# hand.net
KiCad netlist of a schematic drawn in Altium Designer
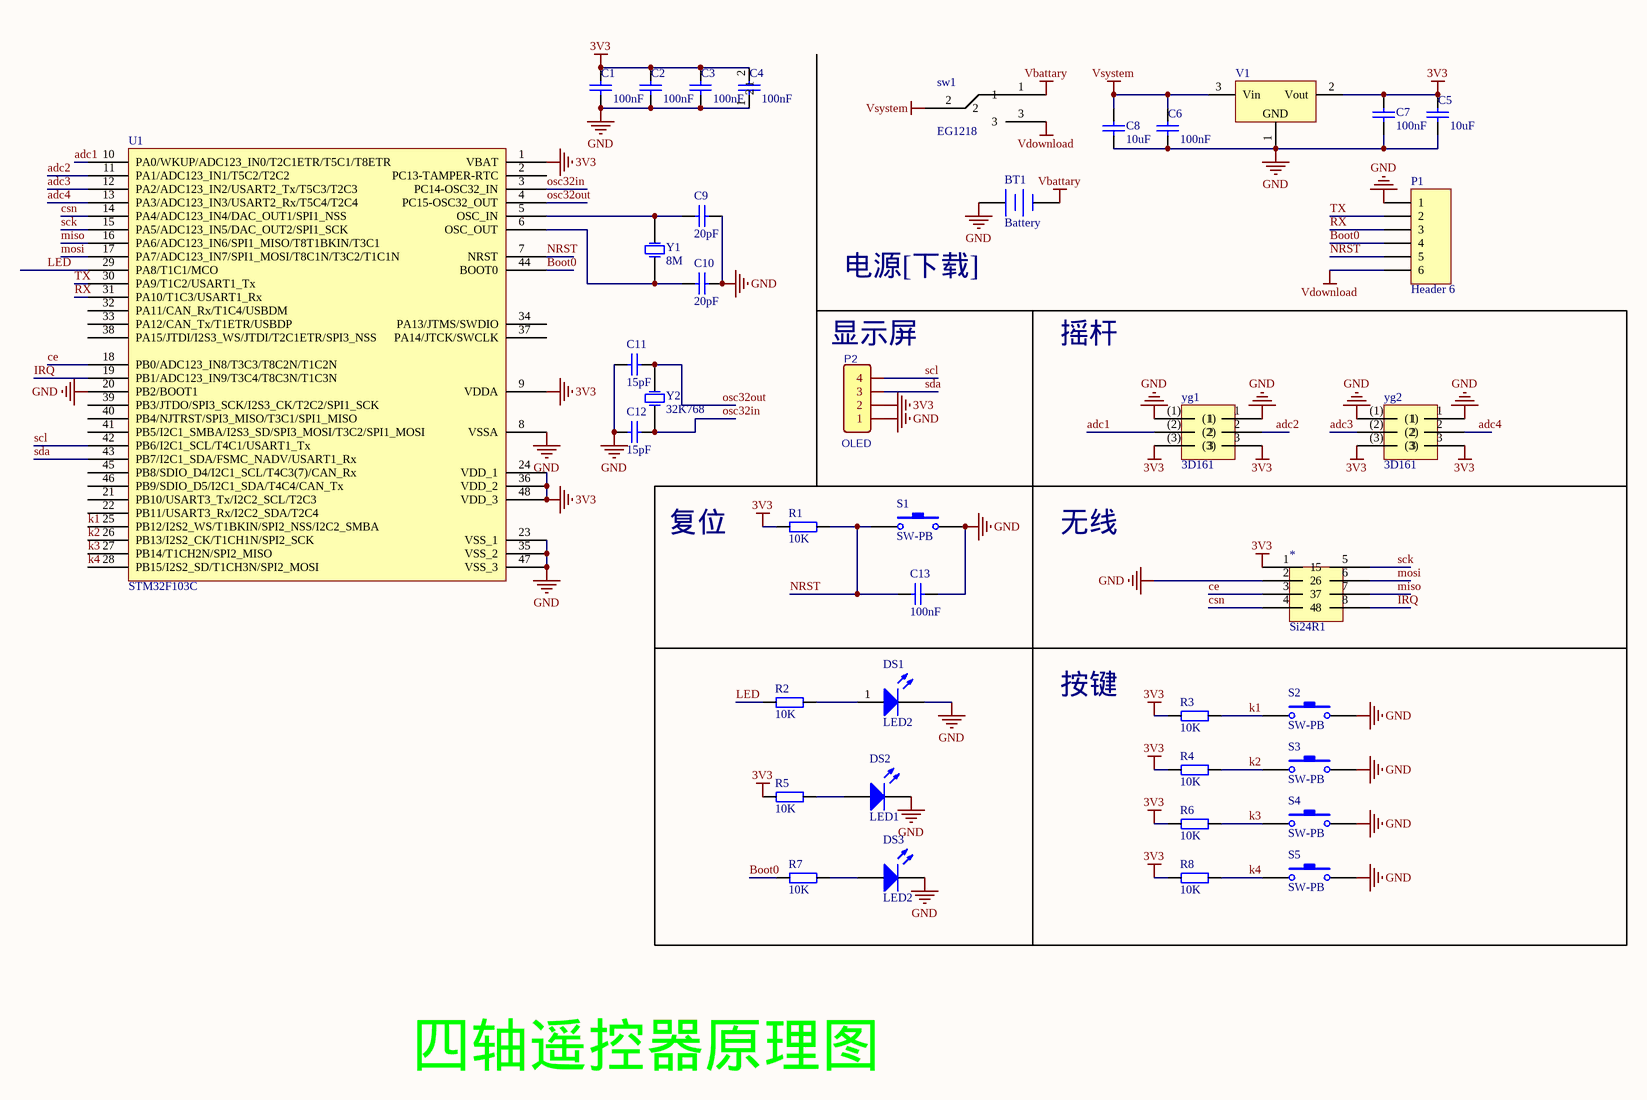
[diagram p0: hand.SchDoc]

(export (version "E")
  (design (tool "Eeschema 10.0.6"))
  (components
    (comp (ref "*")
      (value "Si24R1")
      (footprint "WIRELM-SMD_DL-SI24R1-A")
      (libsource (lib "Schlib1") (part "Si24R1"))
    )
    (comp (ref "BT1")
      (value "Battery")
      (footprint "CONN-TH_2P-P2.00_HDGC_HDGC2001WV-2P")
      (description "采用ph2.0接线端子")
      (fields (field (name "PUBLISHER") "Altium Limited"))
      (libsource (lib "Miscellaneous Devices") (part "Battery"))
    )
    (comp (ref "C1")
      (value "100nF")
      (footprint "C0603")
      (description "Capacitor")
      (fields (field (name "PUBLISHER") "Altium Limited"))
      (libsource (lib "Miscellaneous Devices") (part "Cap"))
    )
    (comp (ref "C2")
      (value "100nF")
      (footprint "C0603")
      (description "Capacitor")
      (fields (field (name "PUBLISHER") "Altium Limited"))
      (libsource (lib "Miscellaneous Devices") (part "Cap"))
    )
    (comp (ref "C3")
      (value "100nF")
      (footprint "C0603")
      (description "Capacitor")
      (fields (field (name "PUBLISHER") "Altium Limited"))
      (libsource (lib "Miscellaneous Devices") (part "Cap"))
    )
    (comp (ref "C4")
      (value "100nF")
      (footprint "C0603")
      (description "Capacitor")
      (fields (field (name "PUBLISHER") "Altium Limited"))
      (libsource (lib "") (part "Cap_1"))
    )
    (comp (ref "C5")
      (value "10uF")
      (footprint "C0603")
      (description "Capacitor")
      (fields (field (name "PUBLISHER") "Altium Limited"))
      (libsource (lib "Miscellaneous Devices") (part "Cap"))
    )
    (comp (ref "C6")
      (value "100nF")
      (footprint "C0603")
      (description "Capacitor")
      (fields (field (name "PUBLISHER") "Altium Limited"))
      (libsource (lib "Miscellaneous Devices") (part "Cap"))
    )
    (comp (ref "C7")
      (value "100nF")
      (footprint "C0603")
      (description "Capacitor")
      (fields (field (name "PUBLISHER") "Altium Limited"))
      (libsource (lib "Miscellaneous Devices") (part "Cap"))
    )
    (comp (ref "C8")
      (value "10uF")
      (footprint "C0603")
      (description "Capacitor")
      (fields (field (name "PUBLISHER") "Altium Limited"))
      (libsource (lib "Miscellaneous Devices") (part "Cap"))
    )
    (comp (ref "C9")
      (value "20pF")
      (footprint "C0603")
      (description "Capacitor")
      (fields (field (name "PUBLISHER") "Altium Limited"))
      (libsource (lib "Miscellaneous Devices") (part "Cap"))
    )
    (comp (ref "C10")
      (value "20pF")
      (footprint "C0603")
      (description "Capacitor")
      (fields (field (name "PUBLISHER") "Altium Limited"))
      (libsource (lib "Miscellaneous Devices") (part "Cap"))
    )
    (comp (ref "C11")
      (value "15pF")
      (footprint "C0603")
      (description "Capacitor")
      (fields (field (name "PUBLISHER") "Altium Limited"))
      (libsource (lib "Miscellaneous Devices") (part "Cap"))
    )
    (comp (ref "C12")
      (value "15pF")
      (footprint "C0603")
      (description "Capacitor")
      (fields (field (name "PUBLISHER") "Altium Limited"))
      (libsource (lib "Miscellaneous Devices") (part "Cap"))
    )
    (comp (ref "C13")
      (value "100nF")
      (footprint "C0603")
      (description "Capacitor")
      (fields (field (name "PUBLISHER") "Altium Limited"))
      (libsource (lib "Miscellaneous Devices") (part "Cap"))
    )
    (comp (ref "DS1")
      (value "LED2")
      (footprint "SMDLED")
      (description "Typical RED, GREEN, YELLOW, AMBER GaAs LED")
      (fields (field (name "PUBLISHER") "Altium Limited"))
      (libsource (lib "") (part "LED2_1"))
    )
    (comp (ref "DS2")
      (value "LED1")
      (footprint "SMDLED")
      (description "Typical RED, GREEN, YELLOW, AMBER GaAs LED")
      (fields (field (name "PUBLISHER") "Altium Limited"))
      (libsource (lib "朱雀F103开发板封装库") (part "LED2"))
    )
    (comp (ref "DS3")
      (value "LED2")
      (footprint "SMDLED")
      (description "Typical RED, GREEN, YELLOW, AMBER GaAs LED")
      (fields (field (name "PUBLISHER") "Altium Limited"))
      (libsource (lib "朱雀F103开发板封装库") (part "LED2"))
    )
    (comp (ref "P1")
      (value "Header 6")
      (footprint "HDR-TH_6P-P2.54-V-M-R2-C3-S2.54-1")
      (description "Header, 6-Pin")
      (fields (field (name "PUBLISHER") "Altium Limited"))
      (libsource (lib "Miscellaneous Connectors") (part "Header 6"))
    )
    (comp (ref "P2")
      (value "OLED")
      (footprint "P04A")
      (fields
        (field (name "BOM_MANUFACTURER PART") "2.54-1*4P母")
        (field (name "BOM_SUPPLIER PART") "C2718488")
        (field (name "CONTRIBUTOR") "PQG2030PQG")
      )
      (libsource (lib "altium-import") (part "root_2_OLED_"))
    )
    (comp (ref "R1") (value "10K") (footprint "0603P") (libsource (lib "朱雀F103开发板封装库") (part "R")))
    (comp (ref "R2") (value "10K") (footprint "0603P") (libsource (lib "朱雀F103开发板封装库") (part "R")))
    (comp (ref "R3") (value "10K") (footprint "0603P") (libsource (lib "朱雀F103开发板封装库") (part "R")))
    (comp (ref "R4") (value "10K") (footprint "0603P") (libsource (lib "朱雀F103开发板封装库") (part "R")))
    (comp (ref "R5") (value "10K") (footprint "0603P") (libsource (lib "朱雀F103开发板封装库") (part "R")))
    (comp (ref "R6") (value "10K") (footprint "0603P") (libsource (lib "朱雀F103开发板封装库") (part "R")))
    (comp (ref "R7") (value "10K") (footprint "0603P") (libsource (lib "朱雀F103开发板封装库") (part "R")))
    (comp (ref "R8") (value "10K") (footprint "0603P") (libsource (lib "朱雀F103开发板封装库") (part "R")))
    (comp (ref "S1")
      (value "SW-PB")
      (footprint "KEY-SMD_L3.9-W3.0-LS5.0")
      (description "Switch")
      (fields (field (name "PUBLISHER") "Altium Limited"))
      (libsource (lib "Miscellaneous Devices") (part "SW-PB"))
    )
    (comp (ref "S2")
      (value "SW-PB")
      (footprint "KEY-SMD_L3.9-W3.0-LS5.0")
      (description "Switch")
      (fields (field (name "PUBLISHER") "Altium Limited"))
      (libsource (lib "Miscellaneous Devices") (part "SW-PB"))
    )
    (comp (ref "S3")
      (value "SW-PB")
      (footprint "KEY-SMD_L3.9-W3.0-LS5.0")
      (description "Switch")
      (fields (field (name "PUBLISHER") "Altium Limited"))
      (libsource (lib "Miscellaneous Devices") (part "SW-PB"))
    )
    (comp (ref "S4")
      (value "SW-PB")
      (footprint "KEY-SMD_L3.9-W3.0-LS5.0")
      (description "Switch")
      (fields (field (name "PUBLISHER") "Altium Limited"))
      (libsource (lib "Miscellaneous Devices") (part "SW-PB"))
    )
    (comp (ref "S5")
      (value "SW-PB")
      (footprint "KEY-SMD_L3.9-W3.0-LS5.0")
      (description "Switch")
      (fields (field (name "PUBLISHER") "Altium Limited"))
      (libsource (lib "Miscellaneous Devices") (part "SW-PB"))
    )
    (comp (ref "sw1") (value "EG1218") (footprint "SW-TH_EG1218") (libsource (lib "Schlib1") (part "EG1218")))
    (comp (ref "U1")
      (value "STM32F103C")
      (footprint "LQFP-48_M")
      (description "STM32单片机48引脚")
      (libsource (lib "STM32芯片") (part "STM32F103C"))
    )
    (comp (ref "V1")
      (value "AMS1117-3V3")
      (footprint "SOT223_L")
      (description "三端稳压芯片")
      (fields (field (name "版权归属") "源创客"))
      (libsource (lib "1.3   - 电源类芯片") (part "AMS1117"))
    )
    (comp (ref "Y1")
      (value "8M")
      (footprint "XTAL(5032)")
      (description "Crystal Oscillator")
      (fields (field (name "PUBLISHER") "Altium Limited"))
      (libsource (lib "Miscellaneous Devices") (part "XTAL"))
    )
    (comp (ref "Y2")
      (value "32K768")
      (footprint "CRYSTAL-SMD_L3.2-W1.5-1")
      (description "Crystal Oscillator")
      (fields (field (name "PUBLISHER") "Altium Limited"))
      (libsource (lib "Miscellaneous Devices") (part "XTAL"))
    )
    (comp (ref "yg1") (value "3D161") (footprint "SW-TH_3D161") (libsource (lib "Schlib1") (part "3D161")))
    (comp (ref "yg2") (value "3D161") (footprint "SW-TH_3D161") (libsource (lib "Schlib1") (part "3D161")))
  )
  (nets
    (net (code "1") (name "/Boot0") (class "Default")
      (node (ref "P1") (pin "4") (pinfunction "4_4") (pintype "passive"))
      (node (ref "R7") (pin "1") (pintype "passive"))
      (node (ref "U1") (pin "44") (pinfunction "BOOT0_44") (pintype "passive"))
    )
    (net (code "2") (name "/IRQ") (class "Default")
      (node (ref "*") (pin "8") (pinfunction "8_8") (pintype "passive"))
      (node (ref "U1") (pin "19") (pinfunction "PB1/ADC123_IN9/T3C4/T8C3N/T1C3N_19") (pintype "passive"))
    )
    (net (code "3") (name "/LED") (class "Default")
      (node (ref "R2") (pin "1") (pintype "passive"))
      (node (ref "U1") (pin "29") (pinfunction "PA8/T1C1/MCO_29") (pintype "passive"))
    )
    (net (code "4") (name "/NRST") (class "Default")
      (node (ref "C13") (pin "1") (pinfunction "1_1") (pintype "passive"))
      (node (ref "P1") (pin "5") (pinfunction "5_5") (pintype "passive"))
      (node (ref "R1") (pin "2") (pintype "passive"))
      (node (ref "S1") (pin "1") (pinfunction "1_1") (pintype "passive"))
      (node (ref "U1") (pin "7") (pinfunction "NRST_7") (pintype "passive"))
    )
    (net (code "5") (name "/RX") (class "Default")
      (node (ref "P1") (pin "3") (pinfunction "3_3") (pintype "passive"))
      (node (ref "U1") (pin "31") (pinfunction "PA10/T1C3/USART1_Rx_31") (pintype "passive"))
    )
    (net (code "6") (name "/TX") (class "Default")
      (node (ref "P1") (pin "2") (pinfunction "2_2") (pintype "passive"))
      (node (ref "U1") (pin "30") (pinfunction "PA9/T1C2/USART1_Tx_30") (pintype "passive"))
    )
    (net (code "7") (name "/adc1") (class "Default")
      (node (ref "U1") (pin "10") (pinfunction "PA0/WKUP/ADC123_IN0/T2C1ETR/T5C1/T8ETR_10") (pintype "passive"))
      (node (ref "yg1") (pin "(2)") (pinfunction "(2)_(2)") (pintype "passive"))
    )
    (net (code "8") (name "/adc2") (class "Default")
      (node (ref "U1") (pin "11") (pinfunction "PA1/ADC123_IN1/T5C2/T2C2_11") (pintype "passive"))
      (node (ref "yg1") (pin "2") (pinfunction "2_2") (pintype "passive"))
    )
    (net (code "9") (name "/adc3") (class "Default")
      (node (ref "U1") (pin "12") (pinfunction "PA2/ADC123_IN2/USART2_Tx/T5C3/T2C3_12") (pintype "passive"))
      (node (ref "yg2") (pin "(2)") (pinfunction "(2)_(2)") (pintype "passive"))
    )
    (net (code "10") (name "/adc4") (class "Default")
      (node (ref "U1") (pin "13") (pinfunction "PA3/ADC123_IN3/USART2_Rx/T5C4/T2C4_13") (pintype "passive"))
      (node (ref "yg2") (pin "2") (pinfunction "2_2") (pintype "passive"))
    )
    (net (code "11") (name "/ce") (class "Default")
      (node (ref "*") (pin "3") (pinfunction "3_3") (pintype "passive"))
      (node (ref "U1") (pin "18") (pinfunction "PB0/ADC123_IN8/T3C3/T8C2N/T1C2N_18") (pintype "passive"))
    )
    (net (code "12") (name "/csn") (class "Default")
      (node (ref "*") (pin "4") (pinfunction "4_4") (pintype "passive"))
      (node (ref "U1") (pin "14") (pinfunction "PA4/ADC123_IN4/DAC_OUT1/SPI1_NSS_14") (pintype "passive"))
    )
    (net (code "13") (name "/k1") (class "Default")
      (node (ref "R3") (pin "2") (pintype "passive"))
      (node (ref "S2") (pin "1") (pinfunction "1_1") (pintype "passive"))
      (node (ref "U1") (pin "25") (pinfunction "PB12/I2S2_WS/T1BKIN/SPI2_NSS/I2C2_SMBA_25") (pintype "passive"))
    )
    (net (code "14") (name "/k2") (class "Default")
      (node (ref "R4") (pin "2") (pintype "passive"))
      (node (ref "S3") (pin "1") (pinfunction "1_1") (pintype "passive"))
      (node (ref "U1") (pin "26") (pinfunction "PB13/I2S2_CK/T1CH1N/SPI2_SCK_26") (pintype "passive"))
    )
    (net (code "15") (name "/k3") (class "Default")
      (node (ref "R6") (pin "2") (pintype "passive"))
      (node (ref "S4") (pin "1") (pinfunction "1_1") (pintype "passive"))
      (node (ref "U1") (pin "27") (pinfunction "PB14/T1CH2N/SPI2_MISO_27") (pintype "passive"))
    )
    (net (code "16") (name "/k4") (class "Default")
      (node (ref "R8") (pin "2") (pintype "passive"))
      (node (ref "S5") (pin "1") (pinfunction "1_1") (pintype "passive"))
      (node (ref "U1") (pin "28") (pinfunction "PB15/I2S2_SD/T1CH3N/SPI2_MOSI_28") (pintype "passive"))
    )
    (net (code "17") (name "/miso") (class "Default")
      (node (ref "*") (pin "7") (pinfunction "7_7") (pintype "passive"))
      (node (ref "U1") (pin "16") (pinfunction "PA6/ADC123_IN6/SPI1_MISO/T8T1BKIN/T3C1_16") (pintype "passive"))
    )
    (net (code "18") (name "/mosi") (class "Default")
      (node (ref "*") (pin "6") (pinfunction "6_6") (pintype "passive"))
      (node (ref "U1") (pin "17") (pinfunction "PA7/ADC123_IN7/SPI1_MOSI/T8C1N/T3C2/T1C1N_17") (pintype "passive"))
    )
    (net (code "19") (name "/osc32in") (class "Default")
      (node (ref "C12") (pin "2") (pinfunction "2_2") (pintype "passive"))
      (node (ref "U1") (pin "3") (pinfunction "PC14-OSC32_IN_3") (pintype "passive"))
      (node (ref "Y2") (pin "1") (pinfunction "OSC1_1") (pintype "passive"))
    )
    (net (code "20") (name "/osc32out") (class "Default")
      (node (ref "C11") (pin "2") (pinfunction "2_2") (pintype "passive"))
      (node (ref "U1") (pin "4") (pinfunction "PC15-OSC32_OUT_4") (pintype "passive"))
      (node (ref "Y2") (pin "2") (pinfunction "OSC2_2") (pintype "passive"))
    )
    (net (code "21") (name "/sck") (class "Default")
      (node (ref "*") (pin "5") (pinfunction "5_5") (pintype "passive"))
      (node (ref "U1") (pin "15") (pinfunction "PA5/ADC123_IN5/DAC_OUT2/SPI1_SCK_15") (pintype "passive"))
    )
    (net (code "22") (name "/scl") (class "Default")
      (node (ref "P2") (pin "4") (pinfunction "4_4") (pintype "passive"))
      (node (ref "U1") (pin "42") (pinfunction "PB6/I2C1_SCL/T4C1/USART1_Tx_42") (pintype "passive"))
    )
    (net (code "23") (name "/sda") (class "Default")
      (node (ref "P2") (pin "3") (pinfunction "3_3") (pintype "passive"))
      (node (ref "U1") (pin "43") (pinfunction "PB7/I2C1_SDA/FSMC_NADV/USART1_Rx_43") (pintype "passive"))
    )
    (net (code "24") (name "3V3") (class "Default")
      (node (ref "*") (pin "1") (pinfunction "1_1") (pintype "passive"))
      (node (ref "C1") (pin "2") (pinfunction "2_2") (pintype "passive"))
      (node (ref "C2") (pin "2") (pinfunction "2_2") (pintype "passive"))
      (node (ref "C3") (pin "2") (pinfunction "2_2") (pintype "passive"))
      (node (ref "C4") (pin "2") (pinfunction "2_2") (pintype "passive"))
      (node (ref "C5") (pin "2") (pinfunction "2_2") (pintype "passive"))
      (node (ref "C7") (pin "2") (pinfunction "2_2") (pintype "passive"))
      (node (ref "P2") (pin "2") (pinfunction "2_2") (pintype "passive"))
      (node (ref "R1") (pin "1") (pintype "passive"))
      (node (ref "R3") (pin "1") (pintype "passive"))
      (node (ref "R4") (pin "1") (pintype "passive"))
      (node (ref "R5") (pin "1") (pintype "passive"))
      (node (ref "R6") (pin "1") (pintype "passive"))
      (node (ref "R8") (pin "1") (pintype "passive"))
      (node (ref "U1") (pin "1") (pinfunction "VBAT_1") (pintype "passive"))
      (node (ref "U1") (pin "24") (pinfunction "VDD_1_24") (pintype "passive"))
      (node (ref "U1") (pin "36") (pinfunction "VDD_2_36") (pintype "passive"))
      (node (ref "U1") (pin "48") (pinfunction "VDD_3_48") (pintype "passive"))
      (node (ref "U1") (pin "9") (pinfunction "VDDA_9") (pintype "passive"))
      (node (ref "V1") (pin "2") (pinfunction "Vout_2") (pintype "passive"))
      (node (ref "yg1") (pin "(3)") (pinfunction "(3)_(3)") (pintype "passive"))
      (node (ref "yg1") (pin "3") (pinfunction "3_3") (pintype "passive"))
      (node (ref "yg2") (pin "(3)") (pinfunction "(3)_(3)") (pintype "passive"))
      (node (ref "yg2") (pin "3") (pinfunction "3_3") (pintype "passive"))
    )
    (net (code "25") (name "GND") (class "Default")
      (node (ref "*") (pin "2") (pinfunction "2_2") (pintype "passive"))
      (node (ref "BT1") (pin "1") (pinfunction "+_1") (pintype "passive"))
      (node (ref "C1") (pin "1") (pinfunction "1_1") (pintype "passive"))
      (node (ref "C10") (pin "2") (pinfunction "2_2") (pintype "passive"))
      (node (ref "C11") (pin "1") (pinfunction "1_1") (pintype "passive"))
      (node (ref "C12") (pin "1") (pinfunction "1_1") (pintype "passive"))
      (node (ref "C13") (pin "2") (pinfunction "2_2") (pintype "passive"))
      (node (ref "C2") (pin "1") (pinfunction "1_1") (pintype "passive"))
      (node (ref "C3") (pin "1") (pinfunction "1_1") (pintype "passive"))
      (node (ref "C4") (pin "1") (pinfunction "1_1") (pintype "passive"))
      (node (ref "C5") (pin "1") (pinfunction "1_1") (pintype "passive"))
      (node (ref "C6") (pin "1") (pinfunction "1_1") (pintype "passive"))
      (node (ref "C7") (pin "1") (pinfunction "1_1") (pintype "passive"))
      (node (ref "C8") (pin "1") (pinfunction "1_1") (pintype "passive"))
      (node (ref "C9") (pin "2") (pinfunction "2_2") (pintype "passive"))
      (node (ref "DS1") (pin "2") (pinfunction "K_2") (pintype "passive"))
      (node (ref "DS2") (pin "2") (pinfunction "K_2") (pintype "passive"))
      (node (ref "DS3") (pin "2") (pinfunction "K_2") (pintype "passive"))
      (node (ref "P1") (pin "1") (pinfunction "1_1") (pintype "passive"))
      (node (ref "P2") (pin "1") (pinfunction "1_1") (pintype "passive"))
      (node (ref "S1") (pin "2") (pinfunction "2_2") (pintype "passive"))
      (node (ref "S2") (pin "2") (pinfunction "2_2") (pintype "passive"))
      (node (ref "S3") (pin "2") (pinfunction "2_2") (pintype "passive"))
      (node (ref "S4") (pin "2") (pinfunction "2_2") (pintype "passive"))
      (node (ref "S5") (pin "2") (pinfunction "2_2") (pintype "passive"))
      (node (ref "U1") (pin "20") (pinfunction "PB2/BOOT1_20") (pintype "passive"))
      (node (ref "U1") (pin "23") (pinfunction "VSS_1_23") (pintype "passive"))
      (node (ref "U1") (pin "35") (pinfunction "VSS_2_35") (pintype "passive"))
      (node (ref "U1") (pin "47") (pinfunction "VSS_3_47") (pintype "passive"))
      (node (ref "U1") (pin "8") (pinfunction "VSSA_8") (pintype "passive"))
      (node (ref "V1") (pin "1") (pinfunction "GND_1") (pintype "passive"))
      (node (ref "yg1") (pin "(1)") (pinfunction "(1)_(1)") (pintype "passive"))
      (node (ref "yg1") (pin "1") (pinfunction "1_1") (pintype "passive"))
      (node (ref "yg2") (pin "(1)") (pinfunction "(1)_(1)") (pintype "passive"))
      (node (ref "yg2") (pin "1") (pinfunction "1_1") (pintype "passive"))
    )
    (net (code "26") (name "Net-(DS1-A)") (class "Default")
      (node (ref "DS1") (pin "1") (pinfunction "A_1") (pintype "passive"))
      (node (ref "R2") (pin "2") (pintype "passive"))
    )
    (net (code "27") (name "Net-(DS2-A)") (class "Default")
      (node (ref "DS2") (pin "1") (pinfunction "A_1") (pintype "passive"))
      (node (ref "R5") (pin "2") (pintype "passive"))
    )
    (net (code "28") (name "Net-(DS3-A)") (class "Default")
      (node (ref "DS3") (pin "1") (pinfunction "A_1") (pintype "passive"))
      (node (ref "R7") (pin "2") (pintype "passive"))
    )
    (net (code "29") (name "Net-(U1-OSC_IN)") (class "Default")
      (node (ref "C9") (pin "1") (pinfunction "1_1") (pintype "passive"))
      (node (ref "U1") (pin "5") (pinfunction "OSC_IN_5") (pintype "passive"))
      (node (ref "Y1") (pin "2") (pinfunction "OSC2_2") (pintype "passive"))
    )
    (net (code "30") (name "Net-(U1-OSC_OUT)") (class "Default")
      (node (ref "C10") (pin "1") (pinfunction "1_1") (pintype "passive"))
      (node (ref "U1") (pin "6") (pinfunction "OSC_OUT_6") (pintype "passive"))
      (node (ref "Y1") (pin "1") (pinfunction "OSC1_1") (pintype "passive"))
    )
    (net (code "31") (name "Vbattary") (class "Default")
      (node (ref "BT1") (pin "2") (pinfunction "-_2") (pintype "passive"))
      (node (ref "sw1") (pin "1") (pinfunction "1_1") (pintype "passive"))
    )
    (net (code "32") (name "Vdownload") (class "Default")
      (node (ref "P1") (pin "6") (pinfunction "6_6") (pintype "passive"))
      (node (ref "sw1") (pin "3") (pinfunction "3_3") (pintype "passive"))
    )
    (net (code "33") (name "Vsystem") (class "Default")
      (node (ref "C6") (pin "2") (pinfunction "2_2") (pintype "passive"))
      (node (ref "C8") (pin "2") (pinfunction "2_2") (pintype "passive"))
      (node (ref "V1") (pin "3") (pinfunction "Vin_3") (pintype "passive"))
      (node (ref "sw1") (pin "2") (pinfunction "2_2") (pintype "passive"))
    )
    (net (code "34") (name "unconnected-(U1-PA11{slash}CAN_Rx{slash}T1C4{slash}USBDM-Pad32)") (class "Default")
      (node (ref "U1") (pin "32") (pinfunction "PA11/CAN_Rx/T1C4/USBDM_32") (pintype "passive"))
    )
    (net (code "35") (name "unconnected-(U1-PA12{slash}CAN_Tx{slash}T1ETR{slash}USBDP-Pad33)") (class "Default")
      (node (ref "U1") (pin "33") (pinfunction "PA12/CAN_Tx/T1ETR/USBDP_33") (pintype "passive"))
    )
    (net (code "36") (name "unconnected-(U1-PA13{slash}JTMS{slash}SWDIO-Pad34)") (class "Default")
      (node (ref "U1") (pin "34") (pinfunction "PA13/JTMS/SWDIO_34") (pintype "passive"))
    )
    (net (code "37") (name "unconnected-(U1-PA14{slash}JTCK{slash}SWCLK-Pad37)") (class "Default")
      (node (ref "U1") (pin "37") (pinfunction "PA14/JTCK/SWCLK_37") (pintype "passive"))
    )
    (net (code "38") (name "unconnected-(U1-PA15{slash}JTDI{slash}I2S3_WS{slash}JTDI{slash}T2C1ETR{slash}SPI3_NSS-Pad38)") (class "Default")
      (node (ref "U1") (pin "38") (pinfunction "PA15/JTDI/I2S3_WS/JTDI/T2C1ETR/SPI3_NSS_38") (pintype "passive"))
    )
    (net (code "39") (name "unconnected-(U1-PB3{slash}JTDO{slash}SPI3_SCK{slash}I2S3_CK{slash}T2C2{slash}SPI1_SCK-Pad39)") (class "Default")
      (node (ref "U1") (pin "39") (pinfunction "PB3/JTDO/SPI3_SCK/I2S3_CK/T2C2/SPI1_SCK_39") (pintype "passive"))
    )
    (net (code "40") (name "unconnected-(U1-PB4{slash}NJTRST{slash}SPI3_MISO{slash}T3C1{slash}SPI1_MISO-Pad40)") (class "Default")
      (node (ref "U1") (pin "40") (pinfunction "PB4/NJTRST/SPI3_MISO/T3C1/SPI1_MISO_40") (pintype "passive"))
    )
    (net (code "41") (name "unconnected-(U1-PB5{slash}I2C1_SMBA{slash}I2S3_SD{slash}SPI3_MOSI{slash}T3C2{slash}SPI1_MOSI-Pad41)") (class "Default")
      (node (ref "U1") (pin "41") (pinfunction "PB5/I2C1_SMBA/I2S3_SD/SPI3_MOSI/T3C2/SPI1_MOSI_41") (pintype "passive"))
    )
    (net (code "42") (name "unconnected-(U1-PB8{slash}SDIO_D4{slash}I2C1_SCL{slash}T4C3(7){slash}CAN_Rx-Pad45)") (class "Default")
      (node (ref "U1") (pin "45") (pinfunction "PB8/SDIO_D4/I2C1_SCL/T4C3(7)/CAN_Rx_45") (pintype "passive"))
    )
    (net (code "43") (name "unconnected-(U1-PB9{slash}SDIO_D5{slash}I2C1_SDA{slash}T4C4{slash}CAN_Tx-Pad46)") (class "Default")
      (node (ref "U1") (pin "46") (pinfunction "PB9/SDIO_D5/I2C1_SDA/T4C4/CAN_Tx_46") (pintype "passive"))
    )
    (net (code "44") (name "unconnected-(U1-PB10{slash}USART3_Tx{slash}I2C2_SCL{slash}T2C3-Pad21)") (class "Default")
      (node (ref "U1") (pin "21") (pinfunction "PB10/USART3_Tx/I2C2_SCL/T2C3_21") (pintype "passive"))
    )
    (net (code "45") (name "unconnected-(U1-PB11{slash}USART3_Rx{slash}I2C2_SDA{slash}T2C4-Pad22)") (class "Default")
      (node (ref "U1") (pin "22") (pinfunction "PB11/USART3_Rx/I2C2_SDA/T2C4_22") (pintype "passive"))
    )
    (net (code "46") (name "unconnected-(U1-PC13-TAMPER-RTC-Pad2)") (class "Default")
      (node (ref "U1") (pin "2") (pinfunction "PC13-TAMPER-RTC_2") (pintype "passive"))
    )
  )
)
